# Reefing-Barometer.net
KiCad netlist of a schematic drawn in Altium Designer
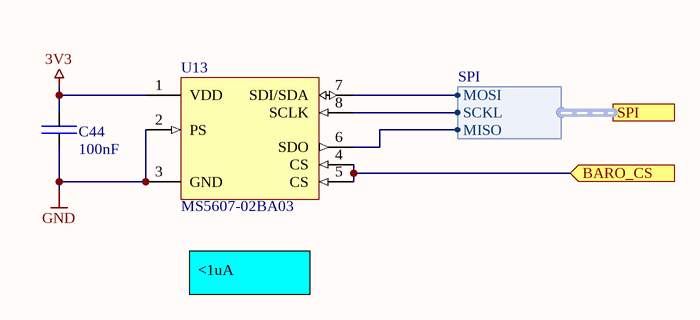
[diagram p0: Reefing-Barometer.SchDoc]

(export (version "E")
  (design (tool "Eeschema 10.0.6"))
  (components
    (comp (ref "C44")
      (value "100nF")
      (footprint "SMD Keramikkondensator 0402")
      (description "SMD Ceramic Capacitor E6")
      (libsource (lib "CATS-EUROC") (part "E6 - 100nF"))
    )
    (comp (ref "U13")
      (value "MS5607-02BA03")
      (footprint "SMD IC BARO MS5607")
      (description "Barometric Pressure Sensor, with stainless\r\nsteel cap")
      (libsource (lib "Sensors") (part "MS5607-02BA03"))
    )
  )
  (nets
    (net (code "2") (name "/BARO_CS") (class "Default")
      (node (ref "U13") (pin "4") (pinfunction "CS_4") (pintype "input"))
      (node (ref "U13") (pin "5") (pinfunction "CS_5") (pintype "input"))
    )
    (net (code "3") (name "/MISO") (class "Default")
      (node (ref "U13") (pin "6") (pinfunction "SDO_6") (pintype "output"))
    )
    (net (code "4") (name "/MOSI") (class "Default")
      (node (ref "U13") (pin "7") (pinfunction "SDI/SDA_7") (pintype "bidirectional"))
    )
    (net (code "5") (name "/SCKL") (class "Default")
      (node (ref "U13") (pin "8") (pinfunction "SCLK_8") (pintype "input"))
    )
    (net (code "7") (name "3V3") (class "Default")
      (node (ref "C44") (pin "2") (pinfunction "2_2") (pintype "passive"))
      (node (ref "U13") (pin "1") (pinfunction "VDD_1") (pintype "passive"))
    )
    (net (code "8") (name "GND") (class "Default")
      (node (ref "C44") (pin "1") (pinfunction "1_1") (pintype "passive"))
      (node (ref "U13") (pin "2") (pinfunction "PS_2") (pintype "input"))
      (node (ref "U13") (pin "3") (pinfunction "GND_3") (pintype "passive"))
    )
  )
)
